# Delay_Chorus_PT2399_CTRL.net
KiCad netlist of a schematic drawn in EAGLE
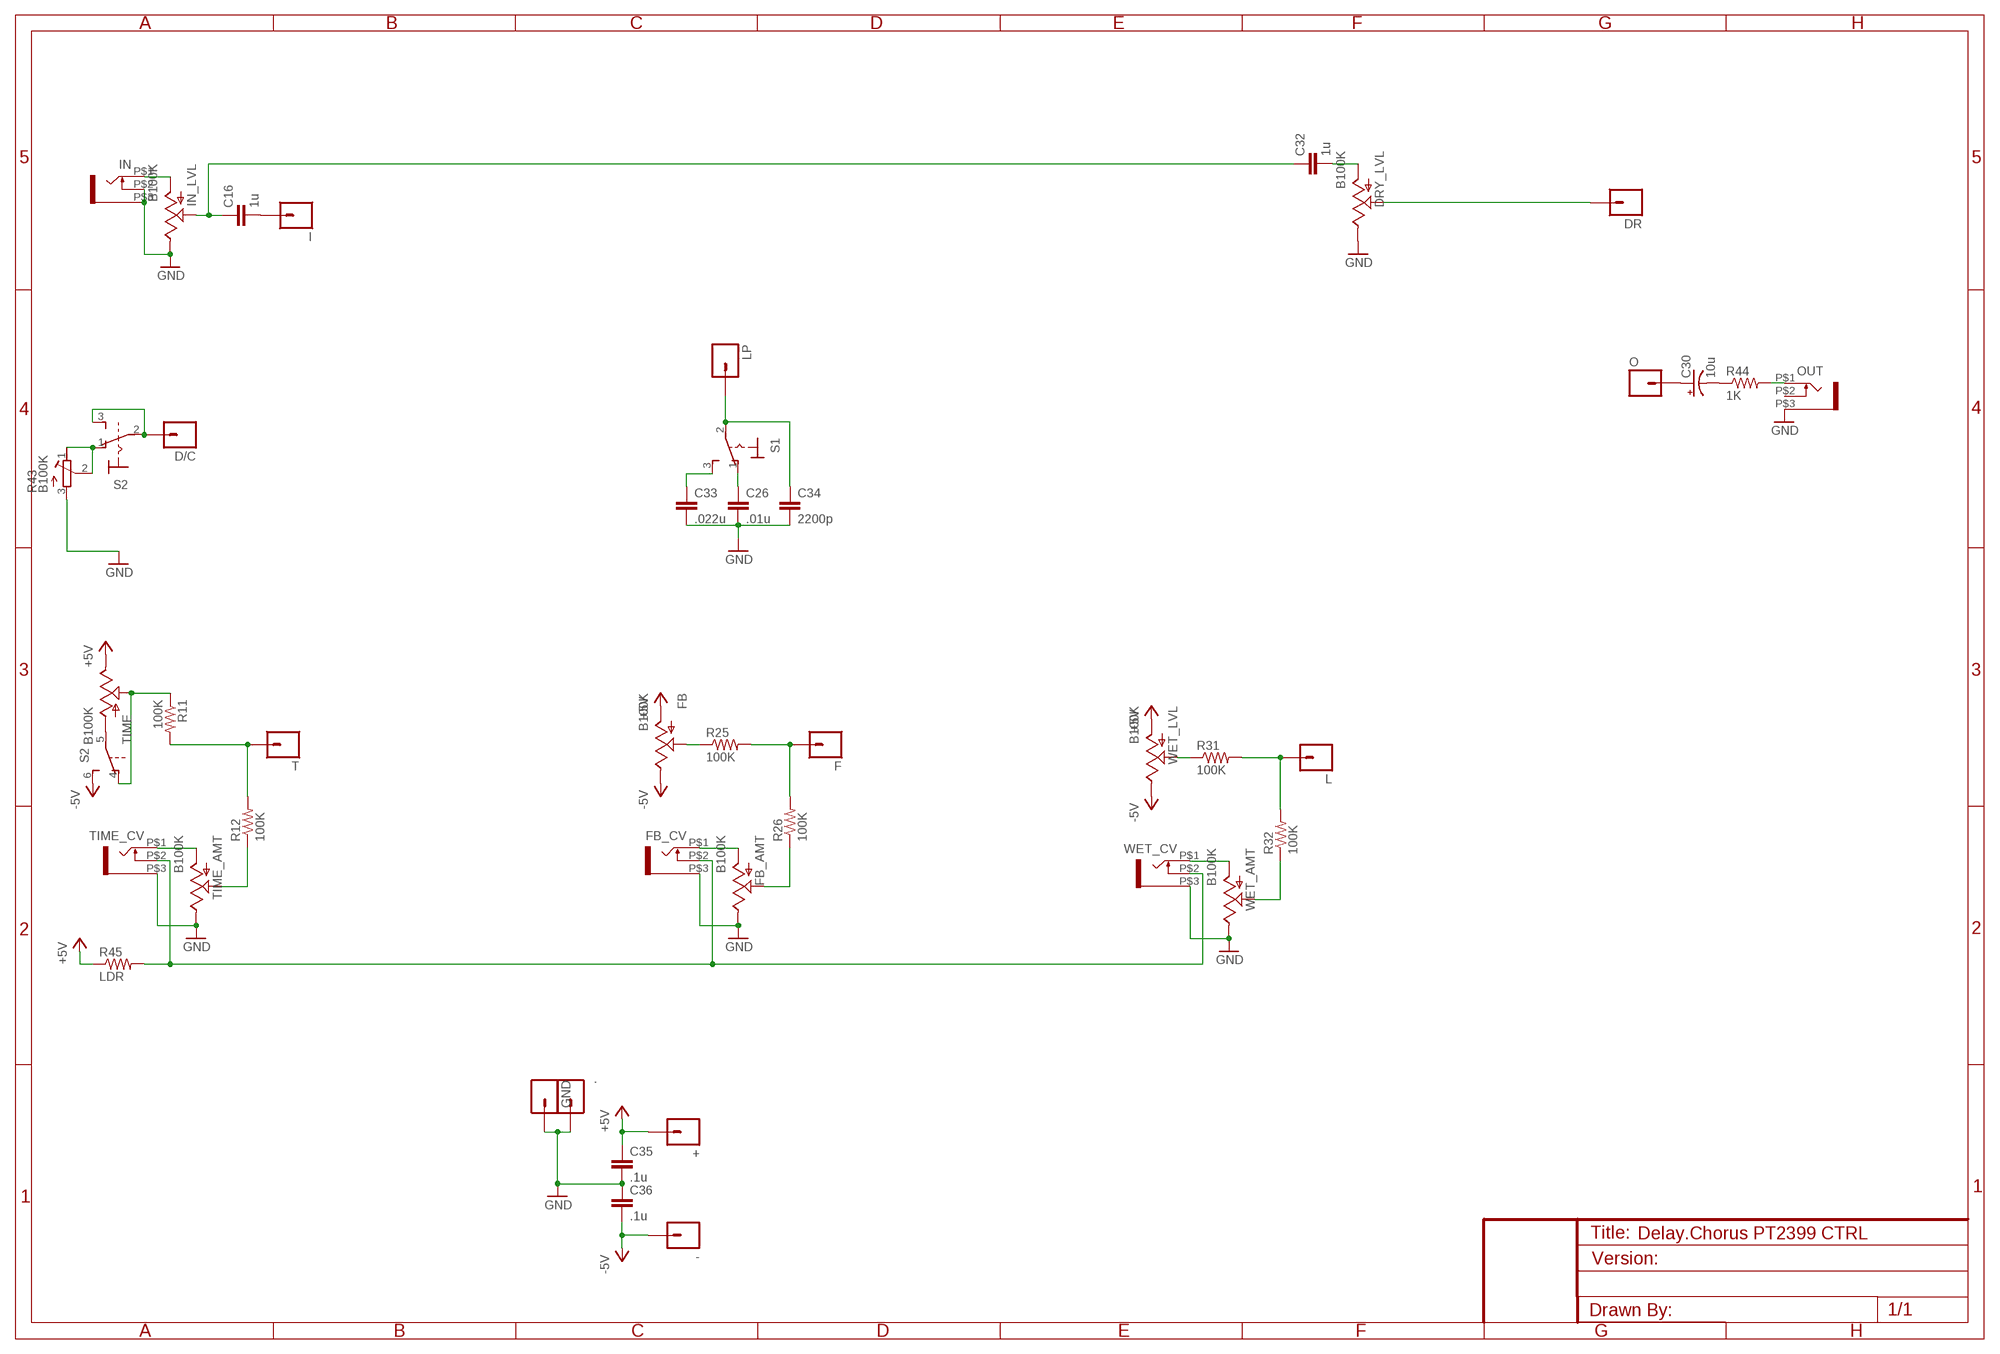
[diagram p0: schematic, sheet 1]

(export (version "E")
  (design (tool "Eeschema 10.0.6"))
  (components
    (comp (ref "+")
      (value "M01PTH")
      (footprint "eagle-import:1X01")
      (libsource (lib "eagle-import") (part "M01PTH"))
    )
    (comp (ref "-")
      (value "M01PTH")
      (footprint "eagle-import:1X01")
      (libsource (lib "eagle-import") (part "M01PTH"))
    )
    (comp (ref ".")
      (value "M01PTH")
      (footprint "eagle-import:1X01")
      (libsource (lib "eagle-import") (part "M01PTH"))
    )
    (comp (ref "C16")
      (value "1u")
      (footprint "eagle-import:1206")
      (libsource (lib "eagle-import") (part "CAP1206"))
    )
    (comp (ref "C26")
      (value ".01u")
      (footprint "eagle-import:C5B2.5")
      (libsource (lib "eagle-import") (part "C5/2.5"))
    )
    (comp (ref "C30")
      (value "10u")
      (footprint "eagle-import:CPOL-RADIAL-10UF-25V")
      (libsource (lib "eagle-import") (part "CAP_POLPTH2"))
    )
    (comp (ref "C32")
      (value "1u")
      (footprint "eagle-import:1206")
      (libsource (lib "eagle-import") (part "CAP1206"))
    )
    (comp (ref "C33")
      (value ".022u")
      (footprint "eagle-import:C5B2.5")
      (libsource (lib "eagle-import") (part "C5/2.5"))
    )
    (comp (ref "C34")
      (value "2200p")
      (footprint "eagle-import:C5B2.5")
      (libsource (lib "eagle-import") (part "C5/2.5"))
    )
    (comp (ref "C35")
      (value ".1u")
      (footprint "eagle-import:0805")
      (libsource (lib "eagle-import") (part "CAP0805"))
    )
    (comp (ref "C36")
      (value ".1u")
      (footprint "eagle-import:0805")
      (libsource (lib "eagle-import") (part "CAP0805"))
    )
    (comp (ref "D/C")
      (value "M01PTH")
      (footprint "eagle-import:1X01")
      (libsource (lib "eagle-import") (part "M01PTH"))
    )
    (comp (ref "DR")
      (value "M01PTH")
      (footprint "eagle-import:1X01")
      (libsource (lib "eagle-import") (part "M01PTH"))
    )
    (comp (ref "DRY_LVL")
      (value "B100K")
      (footprint "eagle-import:ALPS_POT")
      (libsource (lib "eagle-import") (part "POT"))
    )
    (comp (ref "F")
      (value "M01PTH")
      (footprint "eagle-import:1X01")
      (libsource (lib "eagle-import") (part "M01PTH"))
    )
    (comp (ref "FB")
      (value "B100K")
      (footprint "eagle-import:ALPS_POT")
      (libsource (lib "eagle-import") (part "POT"))
    )
    (comp (ref "FB_AMT")
      (value "B100K")
      (footprint "eagle-import:ALPS_POT")
      (libsource (lib "eagle-import") (part "POT"))
    )
    (comp (ref "FB_CV")
      (value "WQP-PJ301M-12_JACK")
      (footprint "eagle-import:WQP-PJ301M-12_JACK")
      (libsource (lib "eagle-import") (part "WQP-PJ301M-12_JACK"))
    )
    (comp (ref "GND")
      (value "M01PTH")
      (footprint "eagle-import:1X01")
      (libsource (lib "eagle-import") (part "M01PTH"))
    )
    (comp (ref "I")
      (value "M01PTH")
      (footprint "eagle-import:1X01")
      (libsource (lib "eagle-import") (part "M01PTH"))
    )
    (comp (ref "IN")
      (value "WQP-PJ301M-12_JACK")
      (footprint "eagle-import:WQP-PJ301M-12_JACK")
      (libsource (lib "eagle-import") (part "WQP-PJ301M-12_JACK"))
    )
    (comp (ref "IN_LVL")
      (value "B100K")
      (footprint "eagle-import:ALPS_POT")
      (libsource (lib "eagle-import") (part "POT"))
    )
    (comp (ref "L")
      (value "M01PTH")
      (footprint "eagle-import:1X01")
      (libsource (lib "eagle-import") (part "M01PTH"))
    )
    (comp (ref "LP")
      (value "M01PTH")
      (footprint "eagle-import:1X01")
      (libsource (lib "eagle-import") (part "M01PTH"))
    )
    (comp (ref "O")
      (value "M01PTH")
      (footprint "eagle-import:1X01")
      (libsource (lib "eagle-import") (part "M01PTH"))
    )
    (comp (ref "OUT")
      (value "WQP-PJ301M-12_JACK")
      (footprint "eagle-import:WQP-PJ301M-12_JACK")
      (libsource (lib "eagle-import") (part "WQP-PJ301M-12_JACK"))
    )
    (comp (ref "R11")
      (value "100K")
      (footprint "eagle-import:0805")
      (libsource (lib "eagle-import") (part "RESISTOR0805-RES"))
    )
    (comp (ref "R12")
      (value "100K")
      (footprint "eagle-import:0805")
      (libsource (lib "eagle-import") (part "RESISTOR0805-RES"))
    )
    (comp (ref "R25")
      (value "100K")
      (footprint "eagle-import:0805")
      (libsource (lib "eagle-import") (part "RESISTOR0805-RES"))
    )
    (comp (ref "R26")
      (value "100K")
      (footprint "eagle-import:0805")
      (libsource (lib "eagle-import") (part "RESISTOR0805-RES"))
    )
    (comp (ref "R31")
      (value "100K")
      (footprint "eagle-import:0805")
      (libsource (lib "eagle-import") (part "RESISTOR0805-RES"))
    )
    (comp (ref "R32")
      (value "100K")
      (footprint "eagle-import:0805")
      (libsource (lib "eagle-import") (part "RESISTOR0805-RES"))
    )
    (comp (ref "R43")
      (value "B100K")
      (footprint "eagle-import:RTRIM3314G")
      (libsource (lib "eagle-import") (part "R-TRIMM3314G"))
    )
    (comp (ref "R44")
      (value "1K")
      (footprint "eagle-import:0805")
      (libsource (lib "eagle-import") (part "RESISTOR0805-RES"))
    )
    (comp (ref "R45")
      (value "LDR")
      (footprint "eagle-import:1_6W-RES")
      (libsource (lib "eagle-import") (part "RESISTORPTH-1/6W"))
    )
    (comp (ref "S1")
      (value "M9040P")
      (footprint "eagle-import:M9040P")
      (libsource (lib "eagle-import") (part "M9040P"))
    )
    (comp (ref "S2")
      (value "M9040P2")
      (footprint "eagle-import:M9040P2")
      (libsource (lib "eagle-import") (part "M9040P2"))
    )
    (comp (ref "T")
      (value "M01PTH")
      (footprint "eagle-import:1X01")
      (libsource (lib "eagle-import") (part "M01PTH"))
    )
    (comp (ref "TIME")
      (value "B100K")
      (footprint "eagle-import:ALPS_POT")
      (libsource (lib "eagle-import") (part "POT"))
    )
    (comp (ref "TIME_AMT")
      (value "B100K")
      (footprint "eagle-import:ALPS_POT")
      (libsource (lib "eagle-import") (part "POT"))
    )
    (comp (ref "TIME_CV")
      (value "WQP-PJ301M-12_JACK")
      (footprint "eagle-import:WQP-PJ301M-12_JACK")
      (libsource (lib "eagle-import") (part "WQP-PJ301M-12_JACK"))
    )
    (comp (ref "WET_AMT")
      (value "B100K")
      (footprint "eagle-import:ALPS_POT")
      (libsource (lib "eagle-import") (part "POT"))
    )
    (comp (ref "WET_CV")
      (value "WQP-PJ301M-12_JACK")
      (footprint "eagle-import:WQP-PJ301M-12_JACK")
      (libsource (lib "eagle-import") (part "WQP-PJ301M-12_JACK"))
    )
    (comp (ref "WET_LVL")
      (value "B100K")
      (footprint "eagle-import:ALPS_POT")
      (libsource (lib "eagle-import") (part "POT"))
    )
  )
  (nets
    (net (code "1") (name "+5V") (class "Default")
      (node (ref "+") (pin "1") (pinfunction "1_1") (pintype "passive"))
      (node (ref "C35") (pin "1") (pinfunction "1_1") (pintype "passive"))
      (node (ref "FB") (pin "P$3") (pinfunction "A_P$3") (pintype "passive"))
      (node (ref "R45") (pin "1") (pinfunction "1_1") (pintype "passive"))
      (node (ref "TIME") (pin "P$1") (pinfunction "E_P$1") (pintype "passive"))
      (node (ref "WET_LVL") (pin "P$3") (pinfunction "A_P$3") (pintype "passive"))
    )
    (net (code "2") (name "-5V") (class "Default")
      (node (ref "-") (pin "1") (pinfunction "1_1") (pintype "passive"))
      (node (ref "C36") (pin "2") (pinfunction "2_2") (pintype "passive"))
      (node (ref "FB") (pin "P$1") (pinfunction "E_P$1") (pintype "passive"))
      (node (ref "S2") (pin "6") (pinfunction "S_6") (pintype "passive"))
      (node (ref "WET_LVL") (pin "P$1") (pinfunction "E_P$1") (pintype "passive"))
    )
    (net (code "3") (name "GND") (class "Default")
      (node (ref ".") (pin "1") (pinfunction "1_1") (pintype "passive"))
      (node (ref "C26") (pin "2") (pinfunction "2_2") (pintype "passive"))
      (node (ref "C33") (pin "2") (pinfunction "2_2") (pintype "passive"))
      (node (ref "C34") (pin "2") (pinfunction "2_2") (pintype "passive"))
      (node (ref "C35") (pin "2") (pinfunction "2_2") (pintype "passive"))
      (node (ref "C36") (pin "1") (pinfunction "1_1") (pintype "passive"))
      (node (ref "DRY_LVL") (pin "P$1") (pinfunction "E_P$1") (pintype "passive"))
      (node (ref "FB_AMT") (pin "P$1") (pinfunction "E_P$1") (pintype "passive"))
      (node (ref "FB_CV") (pin "P$3") (pinfunction "1_P$3") (pintype "passive"))
      (node (ref "GND") (pin "1") (pinfunction "1_1") (pintype "passive"))
      (node (ref "IN") (pin "P$2") (pinfunction "3_P$2") (pintype "passive"))
      (node (ref "IN") (pin "P$3") (pinfunction "1_P$3") (pintype "passive"))
      (node (ref "IN_LVL") (pin "P$1") (pinfunction "E_P$1") (pintype "passive"))
      (node (ref "OUT") (pin "P$3") (pinfunction "1_P$3") (pintype "passive"))
      (node (ref "R43") (pin "3") (pinfunction "A_3") (pintype "passive"))
      (node (ref "TIME_AMT") (pin "P$1") (pinfunction "E_P$1") (pintype "passive"))
      (node (ref "TIME_CV") (pin "P$3") (pinfunction "1_P$3") (pintype "passive"))
      (node (ref "WET_AMT") (pin "P$1") (pinfunction "E_P$1") (pintype "passive"))
      (node (ref "WET_CV") (pin "P$3") (pinfunction "1_P$3") (pintype "passive"))
    )
    (net (code "4") (name "Net-(C16-Pad2)") (class "Default")
      (node (ref "C16") (pin "2") (pinfunction "2_2") (pintype "passive"))
      (node (ref "I") (pin "1") (pinfunction "1_1") (pintype "passive"))
    )
    (net (code "5") (name "Net-(C30-+)") (class "Default")
      (node (ref "C30") (pin "1") (pinfunction "+_1") (pintype "passive"))
      (node (ref "O") (pin "1") (pinfunction "1_1") (pintype "passive"))
    )
    (net (code "6") (name "Net-(C30--)") (class "Default")
      (node (ref "C30") (pin "2") (pinfunction "-_2") (pintype "passive"))
      (node (ref "R44") (pin "1") (pinfunction "1_1") (pintype "passive"))
    )
    (net (code "7") (name "Net-(DRY_LVL-A)") (class "Default")
      (node (ref "C32") (pin "2") (pinfunction "2_2") (pintype "passive"))
      (node (ref "DRY_LVL") (pin "P$3") (pinfunction "A_P$3") (pintype "passive"))
    )
    (net (code "8") (name "Net-(DRY_LVL-S)") (class "Default")
      (node (ref "DR") (pin "1") (pinfunction "1_1") (pintype "passive"))
      (node (ref "DRY_LVL") (pin "P$2") (pinfunction "S_P$2") (pintype "passive"))
    )
    (net (code "9") (name "Net-(F-Pad1)") (class "Default")
      (node (ref "F") (pin "1") (pinfunction "1_1") (pintype "passive"))
      (node (ref "R25") (pin "2") (pinfunction "2_2") (pintype "passive"))
      (node (ref "R26") (pin "2") (pinfunction "2_2") (pintype "passive"))
    )
    (net (code "10") (name "Net-(FB-S)") (class "Default")
      (node (ref "FB") (pin "P$2") (pinfunction "S_P$2") (pintype "passive"))
      (node (ref "R25") (pin "1") (pinfunction "1_1") (pintype "passive"))
    )
    (net (code "11") (name "Net-(FB_AMT-A)") (class "Default")
      (node (ref "FB_AMT") (pin "P$3") (pinfunction "A_P$3") (pintype "passive"))
      (node (ref "FB_CV") (pin "P$1") (pinfunction "2_P$1") (pintype "passive"))
    )
    (net (code "12") (name "Net-(FB_AMT-S)") (class "Default")
      (node (ref "FB_AMT") (pin "P$2") (pinfunction "S_P$2") (pintype "passive"))
      (node (ref "R26") (pin "1") (pinfunction "1_1") (pintype "passive"))
    )
    (net (code "13") (name "Net-(FB_CV-3)") (class "Default")
      (node (ref "FB_CV") (pin "P$2") (pinfunction "3_P$2") (pintype "passive"))
      (node (ref "R45") (pin "2") (pinfunction "2_2") (pintype "passive"))
      (node (ref "TIME_CV") (pin "P$2") (pinfunction "3_P$2") (pintype "passive"))
      (node (ref "WET_CV") (pin "P$2") (pinfunction "3_P$2") (pintype "passive"))
    )
    (net (code "14") (name "Net-(IN-2)") (class "Default")
      (node (ref "IN") (pin "P$1") (pinfunction "2_P$1") (pintype "passive"))
      (node (ref "IN_LVL") (pin "P$3") (pinfunction "A_P$3") (pintype "passive"))
    )
    (net (code "15") (name "Net-(IN_LVL-S)") (class "Default")
      (node (ref "C16") (pin "1") (pinfunction "1_1") (pintype "passive"))
      (node (ref "C32") (pin "1") (pinfunction "1_1") (pintype "passive"))
      (node (ref "IN_LVL") (pin "P$2") (pinfunction "S_P$2") (pintype "passive"))
    )
    (net (code "16") (name "Net-(L-Pad1)") (class "Default")
      (node (ref "L") (pin "1") (pinfunction "1_1") (pintype "passive"))
      (node (ref "R31") (pin "2") (pinfunction "2_2") (pintype "passive"))
      (node (ref "R32") (pin "2") (pinfunction "2_2") (pintype "passive"))
    )
    (net (code "17") (name "Net-(OUT-2)") (class "Default")
      (node (ref "OUT") (pin "P$1") (pinfunction "2_P$1") (pintype "passive"))
      (node (ref "R44") (pin "2") (pinfunction "2_2") (pintype "passive"))
    )
    (net (code "18") (name "Net-(R11-Pad2)") (class "Default")
      (node (ref "R11") (pin "2") (pinfunction "2_2") (pintype "passive"))
      (node (ref "R12") (pin "2") (pinfunction "2_2") (pintype "passive"))
      (node (ref "T") (pin "1") (pinfunction "1_1") (pintype "passive"))
    )
    (net (code "19") (name "Net-(R43-E)") (class "Default")
      (node (ref "R43") (pin "1") (pinfunction "E_1") (pintype "passive"))
      (node (ref "R43") (pin "2") (pinfunction "S_2") (pintype "passive"))
      (node (ref "S2") (pin "1") (pinfunction "O_1") (pintype "passive"))
    )
    (net (code "20") (name "Net-(S1-O)") (class "Default")
      (node (ref "C26") (pin "1") (pinfunction "1_1") (pintype "passive"))
      (node (ref "S1") (pin "1") (pinfunction "O_1") (pintype "passive"))
    )
    (net (code "21") (name "Net-(S1-P)") (class "Default")
      (node (ref "C34") (pin "1") (pinfunction "1_1") (pintype "passive"))
      (node (ref "LP") (pin "1") (pinfunction "1_1") (pintype "passive"))
      (node (ref "S1") (pin "2") (pinfunction "P_2") (pintype "passive"))
    )
    (net (code "22") (name "Net-(S1-S)") (class "Default")
      (node (ref "C33") (pin "1") (pinfunction "1_1") (pintype "passive"))
      (node (ref "S1") (pin "3") (pinfunction "S_3") (pintype "passive"))
    )
    (net (code "23") (name "Net-(S2A-P)") (class "Default")
      (node (ref "D/C") (pin "1") (pinfunction "1_1") (pintype "passive"))
      (node (ref "S2") (pin "2") (pinfunction "P_2") (pintype "passive"))
      (node (ref "S2") (pin "3") (pinfunction "S_3") (pintype "passive"))
    )
    (net (code "24") (name "Net-(S2B-O)") (class "Default")
      (node (ref "R11") (pin "1") (pinfunction "1_1") (pintype "passive"))
      (node (ref "S2") (pin "4") (pinfunction "O_4") (pintype "passive"))
      (node (ref "TIME") (pin "P$2") (pinfunction "S_P$2") (pintype "passive"))
    )
    (net (code "25") (name "Net-(S2B-P)") (class "Default")
      (node (ref "S2") (pin "5") (pinfunction "P_5") (pintype "passive"))
      (node (ref "TIME") (pin "P$3") (pinfunction "A_P$3") (pintype "passive"))
    )
    (net (code "26") (name "Net-(TIME_AMT-A)") (class "Default")
      (node (ref "TIME_AMT") (pin "P$3") (pinfunction "A_P$3") (pintype "passive"))
      (node (ref "TIME_CV") (pin "P$1") (pinfunction "2_P$1") (pintype "passive"))
    )
    (net (code "27") (name "Net-(TIME_AMT-S)") (class "Default")
      (node (ref "R12") (pin "1") (pinfunction "1_1") (pintype "passive"))
      (node (ref "TIME_AMT") (pin "P$2") (pinfunction "S_P$2") (pintype "passive"))
    )
    (net (code "28") (name "Net-(WET_AMT-A)") (class "Default")
      (node (ref "WET_AMT") (pin "P$3") (pinfunction "A_P$3") (pintype "passive"))
      (node (ref "WET_CV") (pin "P$1") (pinfunction "2_P$1") (pintype "passive"))
    )
    (net (code "29") (name "Net-(WET_AMT-S)") (class "Default")
      (node (ref "R32") (pin "1") (pinfunction "1_1") (pintype "passive"))
      (node (ref "WET_AMT") (pin "P$2") (pinfunction "S_P$2") (pintype "passive"))
    )
    (net (code "30") (name "Net-(WET_LVL-S)") (class "Default")
      (node (ref "R31") (pin "1") (pinfunction "1_1") (pintype "passive"))
      (node (ref "WET_LVL") (pin "P$2") (pinfunction "S_P$2") (pintype "passive"))
    )
    (net (code "31") (name "unconnected-(OUT-3-PadP$2)") (class "Default")
      (node (ref "OUT") (pin "P$2") (pinfunction "3_P$2") (pintype "passive"))
    )
  )
)
